# SCH_reaction_2026-08-12.net
KiCad netlist of a schematic drawn in EasyEDA
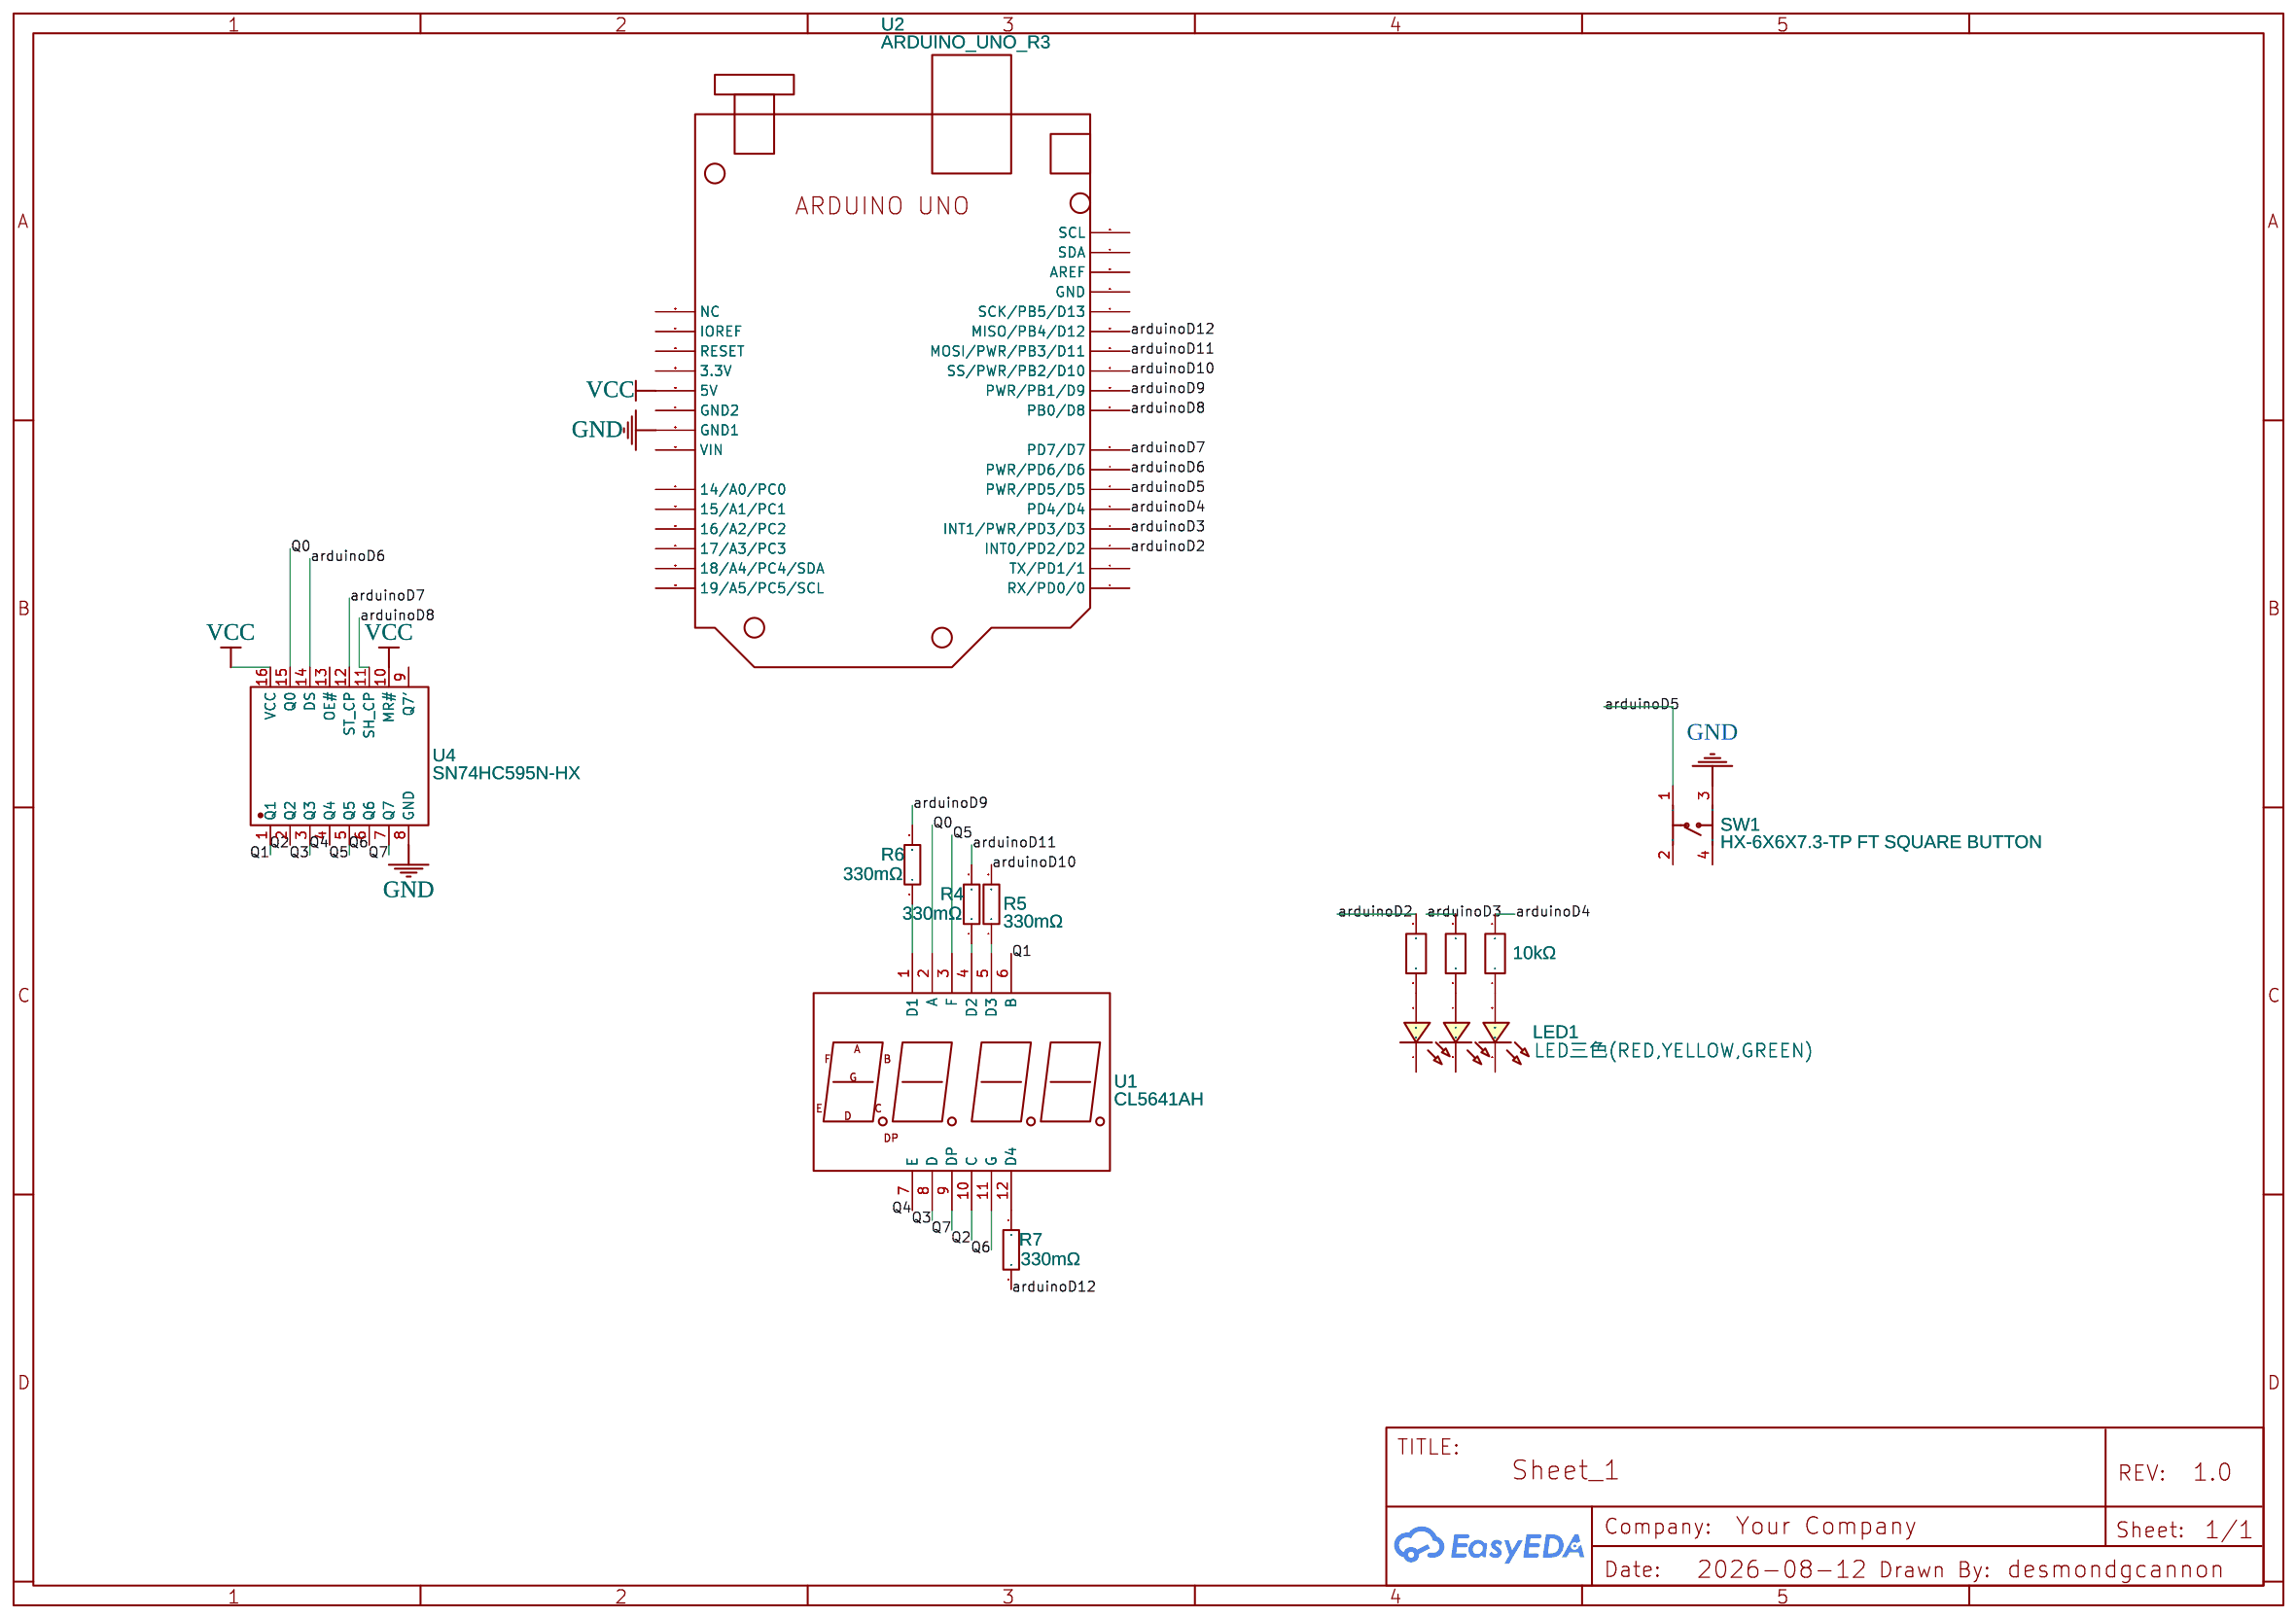
[diagram p0: schematic sheet]

(export (version "E")
  (design (tool "Eeschema 10.0.6"))
  (components
    (comp (ref "LED1")
      (value "LED三色(RED,YELLOW,GREEN)")
      (fields (field (name "Manufacturer Part") "LED三色(Red,Yellow,Green)"))
      (libsource (lib "") (part "LED三色(RED,YELLOW,GREEN)"))
    )
    (comp (ref "R1")
      (value "10kΩ")
      (fields (field (name "Manufacturer Part") "FRC0805J103TS") (field (name "Manufacturer") "FOJAN(富捷)"))
      (libsource (lib "") (part "FRC0805J103TS"))
    )
    (comp (ref "R2")
      (value "10kΩ")
      (fields (field (name "Manufacturer Part") "FRC0805J103TS") (field (name "Manufacturer") "FOJAN(富捷)"))
      (libsource (lib "") (part "FRC0805J103TS"))
    )
    (comp (ref "R3")
      (value "10kΩ")
      (fields (field (name "Manufacturer Part") "FRC0805J103TS") (field (name "Manufacturer") "FOJAN(富捷)"))
      (libsource (lib "") (part "FRC0805J103TS"))
    )
    (comp (ref "R4")
      (value "330mΩ")
      (fields (field (name "Manufacturer Part") "SR732ATTDR330F") (field (name "Manufacturer") "KOA"))
      (libsource (lib "") (part "SR732ATTDR330F_1"))
    )
    (comp (ref "R5")
      (value "330mΩ")
      (fields (field (name "Manufacturer Part") "SR732ATTDR330F") (field (name "Manufacturer") "KOA"))
      (libsource (lib "") (part "SR732ATTDR330F_1"))
    )
    (comp (ref "R6")
      (value "330mΩ")
      (fields (field (name "Manufacturer Part") "SR732ATTDR330F") (field (name "Manufacturer") "KOA"))
      (libsource (lib "") (part "SR732ATTDR330F_1"))
    )
    (comp (ref "R7")
      (value "330mΩ")
      (fields (field (name "Manufacturer Part") "SR732ATTDR330F") (field (name "Manufacturer") "KOA"))
      (libsource (lib "") (part "SR732ATTDR330F"))
    )
    (comp (ref "SW1")
      (value "HX-6X6X7.3-TP FT SQUARE BUTTON")
      (fields
        (field (name "Manufacturer Part") "HX-6x6x7.3-TP FT square button")
        (field (name "Manufacturer") "hanxia(韩下)")
      )
      (libsource (lib "") (part "HX-6X6X7.3-TP FT SQUARE BUTTON"))
    )
    (comp (ref "U1")
      (value "CL5641AH")
      (fields (field (name "Manufacturer") "uxcell"))
      (libsource (lib "") (part "CL5641AH"))
    )
    (comp (ref "U2")
      (value "ARDUINO_UNO_R3")
      (fields (field (name "Manufacturer") "Arduino CC"))
      (libsource (lib "") (part "ARDUINO_UNO_R3"))
    )
    (comp (ref "U4")
      (value "SN74HC595N-HX")
      (fields (field (name "Manufacturer") "ZHHXDZ(海芯电子)"))
      (libsource (lib "") (part "SN74HC595N-HX"))
    )
  )
  (nets
    (net (code "1") (name "/Q0") (class "Default")
      (node (ref "U1") (pin "2") (pinfunction "A_2") (pintype "unspecified"))
      (node (ref "U4") (pin "15") (pinfunction "Q0_15") (pintype "unspecified"))
    )
    (net (code "2") (name "/Q1") (class "Default")
      (node (ref "U1") (pin "6") (pinfunction "B_6") (pintype "unspecified"))
      (node (ref "U4") (pin "1") (pinfunction "Q1_1") (pintype "unspecified"))
    )
    (net (code "3") (name "/Q2") (class "Default")
      (node (ref "U1") (pin "10") (pinfunction "C_10") (pintype "unspecified"))
      (node (ref "U4") (pin "2") (pinfunction "Q2_2") (pintype "unspecified"))
    )
    (net (code "4") (name "/Q3") (class "Default")
      (node (ref "U1") (pin "8") (pinfunction "D_8") (pintype "unspecified"))
      (node (ref "U4") (pin "3") (pinfunction "Q3_3") (pintype "unspecified"))
    )
    (net (code "5") (name "/Q4") (class "Default")
      (node (ref "U1") (pin "7") (pinfunction "E_7") (pintype "unspecified"))
      (node (ref "U4") (pin "4") (pinfunction "Q4_4") (pintype "unspecified"))
    )
    (net (code "6") (name "/Q5") (class "Default")
      (node (ref "U1") (pin "3") (pinfunction "F_3") (pintype "unspecified"))
      (node (ref "U4") (pin "5") (pinfunction "Q5_5") (pintype "unspecified"))
    )
    (net (code "7") (name "/Q6") (class "Default")
      (node (ref "U1") (pin "11") (pinfunction "G_11") (pintype "unspecified"))
      (node (ref "U4") (pin "6") (pinfunction "Q6_6") (pintype "unspecified"))
    )
    (net (code "8") (name "/Q7") (class "Default")
      (node (ref "U1") (pin "9") (pinfunction "DP_9") (pintype "unspecified"))
      (node (ref "U4") (pin "7") (pinfunction "Q7_7") (pintype "unspecified"))
    )
    (net (code "9") (name "/arduinoD2") (class "Default")
      (node (ref "R1") (pin "2") (pinfunction "2_2") (pintype "unspecified"))
      (node (ref "U2") (pin "3") (pinfunction "INT0/PD2/D2_3") (pintype "bidirectional"))
    )
    (net (code "10") (name "/arduinoD3") (class "Default")
      (node (ref "R2") (pin "2") (pinfunction "2_2") (pintype "unspecified"))
      (node (ref "U2") (pin "4") (pinfunction "INT1/PWR/PD3/D3_4") (pintype "bidirectional"))
    )
    (net (code "11") (name "/arduinoD4") (class "Default")
      (node (ref "R3") (pin "2") (pinfunction "2_2") (pintype "unspecified"))
      (node (ref "U2") (pin "5") (pinfunction "PD4/D4_5") (pintype "bidirectional"))
    )
    (net (code "12") (name "/arduinoD5") (class "Default")
      (node (ref "SW1") (pin "1") (pinfunction "A_1") (pintype "unspecified"))
      (node (ref "U2") (pin "6") (pinfunction "PWR/PD5/D5_6") (pintype "bidirectional"))
    )
    (net (code "13") (name "/arduinoD6") (class "Default")
      (node (ref "U2") (pin "7") (pinfunction "PWR/PD6/D6_7") (pintype "bidirectional"))
      (node (ref "U4") (pin "14") (pinfunction "DS_14") (pintype "unspecified"))
    )
    (net (code "14") (name "/arduinoD7") (class "Default")
      (node (ref "U2") (pin "8") (pinfunction "PD7/D7_8") (pintype "bidirectional"))
      (node (ref "U4") (pin "12") (pinfunction "ST_CP_12") (pintype "unspecified"))
    )
    (net (code "15") (name "/arduinoD8") (class "Default")
      (node (ref "U2") (pin "9") (pinfunction "PB0/D8_9") (pintype "bidirectional"))
      (node (ref "U4") (pin "11") (pinfunction "SH_CP_11") (pintype "unspecified"))
    )
    (net (code "16") (name "/arduinoD9") (class "Default")
      (node (ref "R6") (pin "2") (pinfunction "2_2") (pintype "unspecified"))
      (node (ref "U2") (pin "10") (pinfunction "PWR/PB1/D9_10") (pintype "bidirectional"))
    )
    (net (code "17") (name "/arduinoD10") (class "Default")
      (node (ref "R5") (pin "2") (pinfunction "2_2") (pintype "unspecified"))
      (node (ref "U2") (pin "11") (pinfunction "SS/PWR/PB2/D10_11") (pintype "bidirectional"))
    )
    (net (code "18") (name "/arduinoD11") (class "Default")
      (node (ref "R4") (pin "2") (pinfunction "2_2") (pintype "unspecified"))
      (node (ref "U2") (pin "12") (pinfunction "MOSI/PWR/PB3/D11_12") (pintype "bidirectional"))
    )
    (net (code "19") (name "/arduinoD12") (class "Default")
      (node (ref "R7") (pin "2") (pinfunction "2_2") (pintype "unspecified"))
      (node (ref "U2") (pin "13") (pinfunction "MISO/PB4/D12_13") (pintype "bidirectional"))
    )
    (net (code "20") (name "GND") (class "Default")
      (node (ref "SW1") (pin "3") (pinfunction "C_3") (pintype "unspecified"))
      (node (ref "U2") (pin "26") (pinfunction "GND1_26") (pintype "passive"))
      (node (ref "U4") (pin "8") (pinfunction "GND_8") (pintype "unspecified"))
    )
    (net (code "21") (name "Net-(LED1-Pad2)") (class "Default")
      (node (ref "LED1") (pin "2") (pinfunction "2_2") (pintype "unspecified"))
      (node (ref "R1") (pin "1") (pinfunction "1_1") (pintype "unspecified"))
    )
    (net (code "22") (name "Net-(LED1-Pad4)") (class "Default")
      (node (ref "LED1") (pin "4") (pinfunction "4_4") (pintype "unspecified"))
      (node (ref "R2") (pin "1") (pinfunction "1_1") (pintype "unspecified"))
    )
    (net (code "23") (name "Net-(LED1-Pad6)") (class "Default")
      (node (ref "LED1") (pin "6") (pinfunction "6_6") (pintype "unspecified"))
      (node (ref "R3") (pin "1") (pinfunction "1_1") (pintype "unspecified"))
    )
    (net (code "24") (name "Net-(U1-D1)") (class "Default")
      (node (ref "R6") (pin "1") (pinfunction "1_1") (pintype "unspecified"))
      (node (ref "U1") (pin "1") (pinfunction "D1_1") (pintype "unspecified"))
    )
    (net (code "25") (name "Net-(U1-D2)") (class "Default")
      (node (ref "R4") (pin "1") (pinfunction "1_1") (pintype "unspecified"))
      (node (ref "U1") (pin "4") (pinfunction "D2_4") (pintype "unspecified"))
    )
    (net (code "26") (name "Net-(U1-D3)") (class "Default")
      (node (ref "R5") (pin "1") (pinfunction "1_1") (pintype "unspecified"))
      (node (ref "U1") (pin "5") (pinfunction "D3_5") (pintype "unspecified"))
    )
    (net (code "27") (name "Net-(U1-D4)") (class "Default")
      (node (ref "R7") (pin "1") (pinfunction "1_1") (pintype "unspecified"))
      (node (ref "U1") (pin "12") (pinfunction "D4_12") (pintype "unspecified"))
    )
    (net (code "28") (name "VCC") (class "Default")
      (node (ref "U2") (pin "28") (pinfunction "5V_28") (pintype "passive"))
      (node (ref "U4") (pin "10") (pinfunction "MR#_10") (pintype "unspecified"))
      (node (ref "U4") (pin "16") (pinfunction "VCC_16") (pintype "unspecified"))
    )
    (net (code "29") (name "unconnected-(LED1-Pad1)") (class "Default")
      (node (ref "LED1") (pin "1") (pinfunction "1_1") (pintype "unspecified"))
    )
    (net (code "30") (name "unconnected-(LED1-Pad3)") (class "Default")
      (node (ref "LED1") (pin "3") (pinfunction "3_3") (pintype "unspecified"))
    )
    (net (code "31") (name "unconnected-(LED1-Pad5)") (class "Default")
      (node (ref "LED1") (pin "5") (pinfunction "5_5") (pintype "unspecified"))
    )
    (net (code "32") (name "unconnected-(SW1-B-Pad2)") (class "Default")
      (node (ref "SW1") (pin "2") (pinfunction "B_2") (pintype "unspecified"))
    )
    (net (code "33") (name "unconnected-(SW1-D-Pad4)") (class "Default")
      (node (ref "SW1") (pin "4") (pinfunction "D_4") (pintype "unspecified"))
    )
    (net (code "34") (name "unconnected-(U2-3.3V-Pad29)") (class "Default")
      (node (ref "U2") (pin "29") (pinfunction "3.3V_29") (pintype "passive"))
    )
    (net (code "35") (name "unconnected-(U2-14{slash}A0{slash}PC0-Pad24)") (class "Default")
      (node (ref "U2") (pin "24") (pinfunction "14/A0/PC0_24") (pintype "bidirectional"))
    )
    (net (code "36") (name "unconnected-(U2-15{slash}A1{slash}PC1-Pad23)") (class "Default")
      (node (ref "U2") (pin "23") (pinfunction "15/A1/PC1_23") (pintype "bidirectional"))
    )
    (net (code "37") (name "unconnected-(U2-16{slash}A2{slash}PC2-Pad22)") (class "Default")
      (node (ref "U2") (pin "22") (pinfunction "16/A2/PC2_22") (pintype "bidirectional"))
    )
    (net (code "38") (name "unconnected-(U2-17{slash}A3{slash}PC3-Pad21)") (class "Default")
      (node (ref "U2") (pin "21") (pinfunction "17/A3/PC3_21") (pintype "bidirectional"))
    )
    (net (code "39") (name "unconnected-(U2-18{slash}A4{slash}PC4{slash}SDA-Pad20)") (class "Default")
      (node (ref "U2") (pin "20") (pinfunction "18/A4/PC4/SDA_20") (pintype "bidirectional"))
    )
    (net (code "40") (name "unconnected-(U2-19{slash}A5{slash}PC5{slash}SCL-Pad19)") (class "Default")
      (node (ref "U2") (pin "19") (pinfunction "19/A5/PC5/SCL_19") (pintype "bidirectional"))
    )
    (net (code "41") (name "unconnected-(U2-AREF-Pad16)") (class "Default")
      (node (ref "U2") (pin "16") (pinfunction "AREF_16") (pintype "unspecified"))
    )
    (net (code "42") (name "unconnected-(U2-GND-Pad15)") (class "Default")
      (node (ref "U2") (pin "15") (pinfunction "GND_15") (pintype "passive"))
    )
    (net (code "43") (name "unconnected-(U2-GND2-Pad27)") (class "Default")
      (node (ref "U2") (pin "27") (pinfunction "GND2_27") (pintype "passive"))
    )
    (net (code "44") (name "unconnected-(U2-IOREF-Pad31)") (class "Default")
      (node (ref "U2") (pin "31") (pinfunction "IOREF_31") (pintype "unspecified"))
    )
    (net (code "45") (name "unconnected-(U2-NC-Pad32)") (class "Default")
      (node (ref "U2") (pin "32") (pinfunction "NC_32") (pintype "unspecified"))
    )
    (net (code "46") (name "unconnected-(U2-RESET-Pad30)") (class "Default")
      (node (ref "U2") (pin "30") (pinfunction "RESET_30") (pintype "unspecified"))
    )
    (net (code "47") (name "unconnected-(U2-RX{slash}PD0{slash}0-Pad1)") (class "Default")
      (node (ref "U2") (pin "1") (pinfunction "RX/PD0/0_1") (pintype "unspecified"))
    )
    (net (code "48") (name "unconnected-(U2-SCK{slash}PB5{slash}D13-Pad14)") (class "Default")
      (node (ref "U2") (pin "14") (pinfunction "SCK/PB5/D13_14") (pintype "bidirectional"))
    )
    (net (code "49") (name "unconnected-(U2-SCL-Pad18)") (class "Default")
      (node (ref "U2") (pin "18") (pinfunction "SCL_18") (pintype "unspecified"))
    )
    (net (code "50") (name "unconnected-(U2-SDA-Pad17)") (class "Default")
      (node (ref "U2") (pin "17") (pinfunction "SDA_17") (pintype "unspecified"))
    )
    (net (code "51") (name "unconnected-(U2-TX{slash}PD1{slash}1-Pad2)") (class "Default")
      (node (ref "U2") (pin "2") (pinfunction "TX/PD1/1_2") (pintype "unspecified"))
    )
    (net (code "52") (name "unconnected-(U2-VIN-Pad25)") (class "Default")
      (node (ref "U2") (pin "25") (pinfunction "VIN_25") (pintype "passive"))
    )
    (net (code "53") (name "unconnected-(U4-OE#-Pad13)") (class "Default")
      (node (ref "U4") (pin "13") (pinfunction "OE#_13") (pintype "unspecified"))
    )
    (net (code "54") (name "unconnected-(U4-Q7′-Pad9)") (class "Default")
      (node (ref "U4") (pin "9") (pinfunction "Q7′_9") (pintype "unspecified"))
    )
  )
)
